# Sheet1.net
KiCad netlist of a schematic drawn in Altium Designer
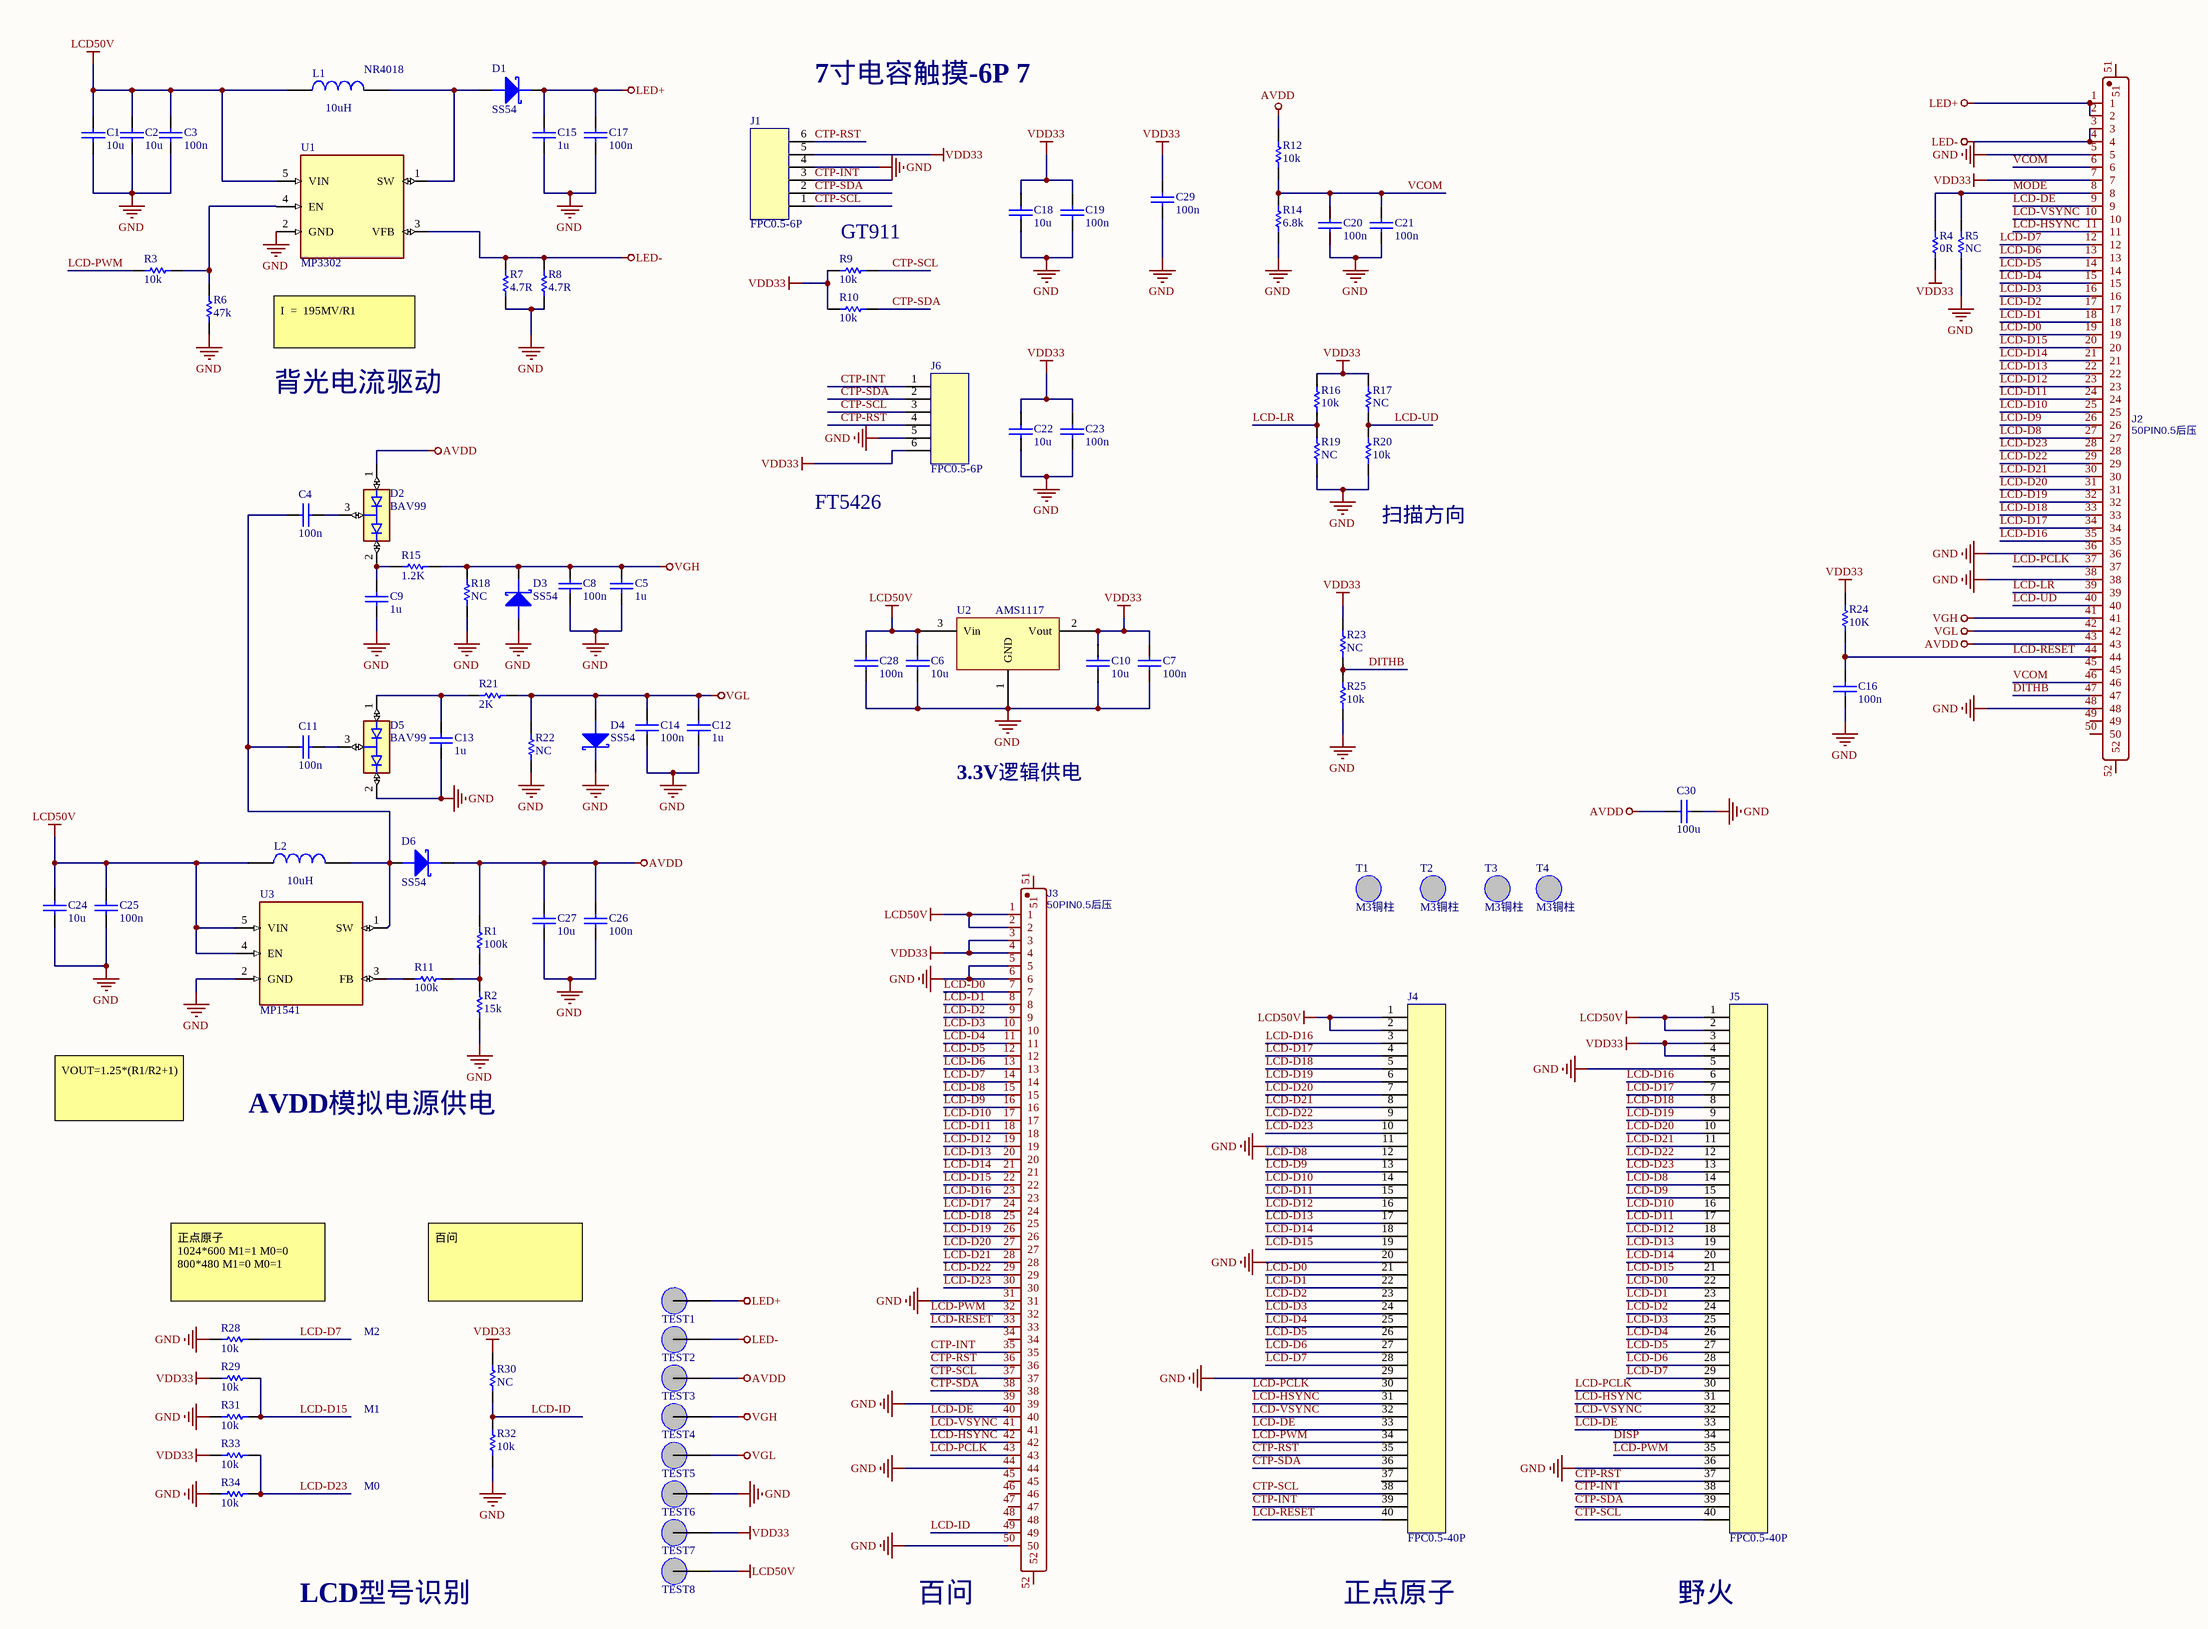
[diagram p0: Sheet1.SchDoc]

(export (version "E")
  (design (tool "Eeschema 10.0.6"))
  (components
    (comp (ref "C1")
      (value "10u")
      (footprint "0805C")
      (description "无极性电容")
      (libsource (lib "常用元件-电容") (part "CAP"))
    )
    (comp (ref "C2")
      (value "10u")
      (footprint "0805C")
      (description "无极性电容")
      (libsource (lib "常用元件-电容") (part "CAP"))
    )
    (comp (ref "C3")
      (value "100n")
      (footprint "0805C")
      (description "无极性电容")
      (libsource (lib "常用元件-电容") (part "CAP"))
    )
    (comp (ref "C4")
      (value "100n")
      (footprint "0805C")
      (description "无极性电容")
      (libsource (lib "常用元件-电容") (part "CAP"))
    )
    (comp (ref "C5")
      (value "1u")
      (footprint "0805C")
      (description "无极性电容")
      (libsource (lib "常用元件-电容") (part "CAP"))
    )
    (comp (ref "C6")
      (value "10u")
      (footprint "0805C")
      (description "无极性电容")
      (libsource (lib "常用元件-电容") (part "CAP"))
    )
    (comp (ref "C7")
      (value "100n")
      (footprint "0805C")
      (description "无极性电容")
      (libsource (lib "常用元件-电容") (part "CAP"))
    )
    (comp (ref "C8")
      (value "100n")
      (footprint "0805C")
      (description "无极性电容")
      (libsource (lib "常用元件-电容") (part "CAP"))
    )
    (comp (ref "C9")
      (value "1u")
      (footprint "0805C")
      (description "无极性电容")
      (libsource (lib "常用元件-电容") (part "CAP"))
    )
    (comp (ref "C10")
      (value "10u")
      (footprint "0805C")
      (description "无极性电容")
      (libsource (lib "常用元件-电容") (part "CAP"))
    )
    (comp (ref "C11")
      (value "100n")
      (footprint "0805C")
      (description "无极性电容")
      (libsource (lib "常用元件-电容") (part "CAP"))
    )
    (comp (ref "C12")
      (value "1u")
      (footprint "0805C")
      (description "无极性电容")
      (libsource (lib "常用元件-电容") (part "CAP"))
    )
    (comp (ref "C13")
      (value "1u")
      (footprint "0805C")
      (description "无极性电容")
      (libsource (lib "常用元件-电容") (part "CAP"))
    )
    (comp (ref "C14")
      (value "100n")
      (footprint "0805C")
      (description "无极性电容")
      (libsource (lib "常用元件-电容") (part "CAP"))
    )
    (comp (ref "C15")
      (value "1u")
      (footprint "0805C")
      (description "无极性电容")
      (libsource (lib "常用元件-电容") (part "CAP"))
    )
    (comp (ref "C16")
      (value "100n")
      (footprint "0805C")
      (description "无极性电容")
      (libsource (lib "常用元件-电容") (part "CAP"))
    )
    (comp (ref "C17")
      (value "100n")
      (footprint "0805C")
      (description "无极性电容")
      (libsource (lib "常用元件-电容") (part "CAP"))
    )
    (comp (ref "C18")
      (value "10u")
      (footprint "0805C")
      (description "无极性电容")
      (libsource (lib "常用元件-电容") (part "CAP"))
    )
    (comp (ref "C19")
      (value "100n")
      (footprint "0805C")
      (description "无极性电容")
      (libsource (lib "常用元件-电容") (part "CAP"))
    )
    (comp (ref "C20")
      (value "100n")
      (footprint "0805C")
      (description "无极性电容")
      (libsource (lib "常用元件-电容") (part "CAP"))
    )
    (comp (ref "C21")
      (value "100n")
      (footprint "0805C")
      (description "无极性电容")
      (libsource (lib "常用元件-电容") (part "CAP"))
    )
    (comp (ref "C22")
      (value "10u")
      (footprint "0805C")
      (description "无极性电容")
      (libsource (lib "常用元件-电容") (part "CAP"))
    )
    (comp (ref "C23")
      (value "100n")
      (footprint "0805C")
      (description "无极性电容")
      (libsource (lib "常用元件-电容") (part "CAP"))
    )
    (comp (ref "C24")
      (value "10u")
      (footprint "0805C")
      (description "无极性电容")
      (libsource (lib "常用元件-电容") (part "CAP"))
    )
    (comp (ref "C25")
      (value "100n")
      (footprint "0805C")
      (description "无极性电容")
      (libsource (lib "常用元件-电容") (part "CAP"))
    )
    (comp (ref "C26")
      (value "100n")
      (footprint "0805C")
      (description "无极性电容")
      (libsource (lib "常用元件-电容") (part "CAP"))
    )
    (comp (ref "C27")
      (value "10u")
      (footprint "0805C")
      (description "无极性电容")
      (libsource (lib "常用元件-电容") (part "CAP"))
    )
    (comp (ref "C28")
      (value "100n")
      (footprint "0805C")
      (description "无极性电容")
      (libsource (lib "常用元件-电容") (part "CAP"))
    )
    (comp (ref "C29")
      (value "100n")
      (footprint "0805C")
      (description "无极性电容")
      (libsource (lib "常用元件-电容") (part "CAP"))
    )
    (comp (ref "C30")
      (value "100u")
      (footprint "1206C")
      (description "无极性电容")
      (libsource (lib "常用元件-电容") (part "CAP"))
    )
    (comp (ref "D1")
      (value "SS54")
      (footprint "SOD-123")
      (description "肖特基二极管")
      (libsource (lib "常用元件-二极管") (part "DIODE SCHOTTKY"))
    )
    (comp (ref "D2")
      (value "BAV99")
      (footprint "BAV99:SOT23-3")
      (fields (field (name "MF") "{'manufacturer': u'ON Semiconductor'}"))
      (libsource (lib "*") (part "BAV99"))
    )
    (comp (ref "D3")
      (value "SS54")
      (footprint "SOD-123")
      (description "肖特基二极管")
      (libsource (lib "常用元件-二极管") (part "DIODE SCHOTTKY"))
    )
    (comp (ref "D4")
      (value "SS54")
      (footprint "SOD-123")
      (description "肖特基二极管")
      (libsource (lib "常用元件-二极管") (part "DIODE SCHOTTKY"))
    )
    (comp (ref "D5")
      (value "BAV99")
      (footprint "BAV99:SOT23-3")
      (fields (field (name "MF") "{'manufacturer': u'ON Semiconductor'}"))
      (libsource (lib "*") (part "BAV99"))
    )
    (comp (ref "D6")
      (value "SS54")
      (footprint "SOD-123")
      (description "肖特基二极管")
      (libsource (lib "常用元件-二极管") (part "DIODE SCHOTTKY"))
    )
    (comp (ref "J1")
      (value "FPC0.5-6P")
      (footprint "FPC0.5-6P")
      (description "贴片")
      (libsource (lib "") (part "FPC0.5-6P_1"))
    )
    (comp (ref "J2")
      (value "50PIN0.5后压")
      (footprint "FPC-SMD_KH-FG0.5-H2.0-50PIN")
      (fields (field (name "BOM_SUPPLIER PART") "C9900011403") (field (name "CONTRIBUTOR") "LCSC"))
      (libsource (lib "altium-import") (part "root_0_50PIN0.5后压_"))
    )
    (comp (ref "J3")
      (value "50PIN0.5后压")
      (footprint "FPC-SMD_KH-FG0.5-H2.0-50PIN")
      (fields (field (name "BOM_SUPPLIER PART") "C9900011403") (field (name "CONTRIBUTOR") "LCSC"))
      (libsource (lib "altium-import") (part "root_0_50PIN0.5后压_"))
    )
    (comp (ref "J4")
      (value "FPC0.5-40P")
      (footprint "FPC0.5-40P")
      (description "贴片")
      (libsource (lib "插接类-FPC") (part "FPC0.5-40P"))
    )
    (comp (ref "J5")
      (value "FPC0.5-40P")
      (footprint "FPC0.5-40P")
      (description "贴片")
      (libsource (lib "插接类-FPC") (part "FPC0.5-40P"))
    )
    (comp (ref "J6")
      (value "FPC0.5-6P")
      (footprint "FPC0.5-6P")
      (description "贴片")
      (libsource (lib "插接类-FPC") (part "FPC0.5-6P"))
    )
    (comp (ref "L1")
      (value "10uH")
      (footprint "CD42")
      (description "INDUCTOR")
      (libsource (lib "常用元件-电感") (part "INDUCTOR"))
    )
    (comp (ref "L2")
      (value "10uH")
      (footprint "CD42")
      (description "INDUCTOR")
      (libsource (lib "常用元件-电感") (part "INDUCTOR"))
    )
    (comp (ref "R1") (value "100k") (footprint "0805R") (libsource (lib "常用元件-电阻") (part "RES")))
    (comp (ref "R2") (value "15k") (footprint "0805R") (libsource (lib "常用元件-电阻") (part "RES")))
    (comp (ref "R3") (value "10k") (footprint "0805R") (libsource (lib "常用元件-电阻") (part "RES")))
    (comp (ref "R4") (value "0R") (footprint "0805R") (libsource (lib "常用元件-电阻") (part "RES")))
    (comp (ref "R5") (value "NC") (footprint "0805R") (libsource (lib "常用元件-电阻") (part "RES")))
    (comp (ref "R6") (value "47k") (footprint "0805R") (libsource (lib "常用元件-电阻") (part "RES")))
    (comp (ref "R7") (value "4.7R") (footprint "0805R") (libsource (lib "常用元件-电阻") (part "RES")))
    (comp (ref "R8") (value "4.7R") (footprint "0805R") (libsource (lib "常用元件-电阻") (part "RES")))
    (comp (ref "R9") (value "10k") (footprint "0805R") (libsource (lib "常用元件-电阻") (part "RES")))
    (comp (ref "R10") (value "10k") (footprint "0805R") (libsource (lib "常用元件-电阻") (part "RES")))
    (comp (ref "R11") (value "100k") (footprint "0805R") (libsource (lib "常用元件-电阻") (part "RES")))
    (comp (ref "R12") (value "10k") (footprint "0805R") (libsource (lib "常用元件-电阻") (part "RES")))
    (comp (ref "R14") (value "6.8k") (footprint "0805R") (libsource (lib "常用元件-电阻") (part "RES")))
    (comp (ref "R15") (value "1.2K") (footprint "0805R") (libsource (lib "常用元件-电阻") (part "RES")))
    (comp (ref "R16") (value "10k") (footprint "0805R") (libsource (lib "常用元件-电阻") (part "RES")))
    (comp (ref "R17") (value "NC") (footprint "0805R") (libsource (lib "常用元件-电阻") (part "RES")))
    (comp (ref "R18") (value "NC") (footprint "0805R") (libsource (lib "常用元件-电阻") (part "RES")))
    (comp (ref "R19") (value "NC") (footprint "0805R") (libsource (lib "常用元件-电阻") (part "RES")))
    (comp (ref "R20") (value "10k") (footprint "0805R") (libsource (lib "常用元件-电阻") (part "RES")))
    (comp (ref "R21") (value "2K") (footprint "0805R") (libsource (lib "常用元件-电阻") (part "RES")))
    (comp (ref "R22") (value "NC") (footprint "0805R") (libsource (lib "常用元件-电阻") (part "RES")))
    (comp (ref "R23") (value "NC") (footprint "0805R") (libsource (lib "常用元件-电阻") (part "RES")))
    (comp (ref "R24") (value "10K") (footprint "0805R") (libsource (lib "常用元件-电阻") (part "RES")))
    (comp (ref "R25") (value "10k") (footprint "0805R") (libsource (lib "常用元件-电阻") (part "RES")))
    (comp (ref "R28") (value "10k") (footprint "0805R") (libsource (lib "常用元件-电阻") (part "RES")))
    (comp (ref "R29") (value "10k") (footprint "0805R") (libsource (lib "常用元件-电阻") (part "RES")))
    (comp (ref "R30") (value "NC") (footprint "0805R") (libsource (lib "常用元件-电阻") (part "RES")))
    (comp (ref "R31") (value "10k") (footprint "0805R") (libsource (lib "常用元件-电阻") (part "RES")))
    (comp (ref "R32") (value "10k") (footprint "0805R") (libsource (lib "常用元件-电阻") (part "RES")))
    (comp (ref "R33") (value "10k") (footprint "0805R") (libsource (lib "常用元件-电阻") (part "RES")))
    (comp (ref "R34") (value "10k") (footprint "0805R") (libsource (lib "常用元件-电阻") (part "RES")))
    (comp (ref "T1") (value "M3铜柱") (footprint "M3 单孔") (libsource (lib "M3铜柱") (part "M3铜柱")))
    (comp (ref "T2") (value "M3铜柱") (footprint "M3 单孔") (libsource (lib "M3铜柱") (part "M3铜柱")))
    (comp (ref "T3") (value "M3铜柱") (footprint "M3 单孔") (libsource (lib "M3铜柱") (part "M3铜柱")))
    (comp (ref "T4") (value "M3铜柱") (footprint "M3 单孔") (libsource (lib "M3铜柱") (part "M3铜柱")))
    (comp (ref "TEST1")
      (value "TEST")
      (footprint "TEST TP1.4_G")
      (description "测试针")
      (fields (field (name "版权归属") "源创客"))
      (libsource (lib "测试类-测试针") (part "TEST"))
    )
    (comp (ref "TEST2")
      (value "TEST")
      (footprint "TEST TP1.4_G")
      (description "测试针")
      (fields (field (name "版权归属") "源创客"))
      (libsource (lib "测试类-测试针") (part "TEST"))
    )
    (comp (ref "TEST3")
      (value "TEST")
      (footprint "TEST TP1.4_G")
      (description "测试针")
      (fields (field (name "版权归属") "源创客"))
      (libsource (lib "测试类-测试针") (part "TEST"))
    )
    (comp (ref "TEST4")
      (value "TEST")
      (footprint "TEST TP1.4_G")
      (description "测试针")
      (fields (field (name "版权归属") "源创客"))
      (libsource (lib "测试类-测试针") (part "TEST"))
    )
    (comp (ref "TEST5")
      (value "TEST")
      (footprint "TEST TP1.4_G")
      (description "测试针")
      (fields (field (name "版权归属") "源创客"))
      (libsource (lib "测试类-测试针") (part "TEST"))
    )
    (comp (ref "TEST6")
      (value "TEST")
      (footprint "TEST TP1.4_G")
      (description "测试针")
      (fields (field (name "版权归属") "源创客"))
      (libsource (lib "测试类-测试针") (part "TEST"))
    )
    (comp (ref "TEST7")
      (value "TEST")
      (footprint "TEST TP1.4_G")
      (description "测试针")
      (fields (field (name "版权归属") "源创客"))
      (libsource (lib "测试类-测试针") (part "TEST"))
    )
    (comp (ref "TEST8")
      (value "TEST")
      (footprint "TEST TP1.4_G")
      (description "测试针")
      (fields (field (name "版权归属") "源创客"))
      (libsource (lib "测试类-测试针") (part "TEST"))
    )
    (comp (ref "U1")
      (value "MP3302")
      (footprint "SOT95P280X100-5N")
      (fields
        (field (name "MP") "TPS563201DDCR")
        (field (name "MF") "{'manufacturer': u'Texas Instruments'}")
      )
      (libsource (lib "MP3302") (part "MP3302"))
    )
    (comp (ref "U2")
      (value "AMS1117")
      (footprint "SOT223")
      (description "三端稳压芯片")
      (libsource (lib "芯片-电源芯片") (part "AMS1117"))
    )
    (comp (ref "U3")
      (value "MP1541")
      (footprint "SOT95P280X100-5N")
      (fields
        (field (name "MP") "TPS563201DDCR")
        (field (name "MF") "{'manufacturer': u'Texas Instruments'}")
      )
      (libsource (lib "MP1541") (part "MP1541"))
    )
  )
  (nets
    (net (code "1") (name "/CTP-INT") (class "Default")
      (node (ref "J1") (pin "3") (pinfunction "3_3") (pintype "passive"))
      (node (ref "J3") (pin "35") (pinfunction "35_35") (pintype "passive"))
      (node (ref "J4") (pin "39") (pinfunction "39_39") (pintype "passive"))
      (node (ref "J5") (pin "38") (pinfunction "38_38") (pintype "passive"))
      (node (ref "J6") (pin "1") (pinfunction "1_1") (pintype "passive"))
    )
    (net (code "2") (name "/CTP-RST") (class "Default")
      (node (ref "J1") (pin "6") (pinfunction "6_6") (pintype "passive"))
      (node (ref "J3") (pin "36") (pinfunction "36_36") (pintype "passive"))
      (node (ref "J4") (pin "35") (pinfunction "35_35") (pintype "passive"))
      (node (ref "J5") (pin "37") (pinfunction "37_37") (pintype "passive"))
      (node (ref "J6") (pin "4") (pinfunction "4_4") (pintype "passive"))
    )
    (net (code "3") (name "/CTP-SCL") (class "Default")
      (node (ref "J1") (pin "1") (pinfunction "1_1") (pintype "passive"))
      (node (ref "J3") (pin "37") (pinfunction "37_37") (pintype "passive"))
      (node (ref "J4") (pin "38") (pinfunction "38_38") (pintype "passive"))
      (node (ref "J5") (pin "40") (pinfunction "40_40") (pintype "passive"))
      (node (ref "J6") (pin "3") (pinfunction "3_3") (pintype "passive"))
      (node (ref "R9") (pin "1") (pinfunction "1_1") (pintype "passive"))
    )
    (net (code "4") (name "/CTP-SDA") (class "Default")
      (node (ref "J1") (pin "2") (pinfunction "2_2") (pintype "passive"))
      (node (ref "J3") (pin "38") (pinfunction "38_38") (pintype "passive"))
      (node (ref "J4") (pin "36") (pinfunction "36_36") (pintype "passive"))
      (node (ref "J5") (pin "39") (pinfunction "39_39") (pintype "passive"))
      (node (ref "J6") (pin "2") (pinfunction "2_2") (pintype "passive"))
      (node (ref "R10") (pin "1") (pinfunction "1_1") (pintype "passive"))
    )
    (net (code "5") (name "/DISP") (class "Default")
      (node (ref "J5") (pin "34") (pinfunction "34_34") (pintype "passive"))
    )
    (net (code "6") (name "/DITHB") (class "Default")
      (node (ref "J2") (pin "47") (pinfunction "47_47") (pintype "passive"))
      (node (ref "R23") (pin "2") (pinfunction "2_2") (pintype "passive"))
      (node (ref "R25") (pin "1") (pinfunction "1_1") (pintype "passive"))
    )
    (net (code "7") (name "/LCD-D0") (class "Default")
      (node (ref "J2") (pin "19") (pinfunction "19_19") (pintype "passive"))
      (node (ref "J3") (pin "7") (pinfunction "7_7") (pintype "passive"))
      (node (ref "J4") (pin "21") (pinfunction "21_21") (pintype "passive"))
      (node (ref "J5") (pin "22") (pinfunction "22_22") (pintype "passive"))
    )
    (net (code "8") (name "/LCD-D1") (class "Default")
      (node (ref "J2") (pin "18") (pinfunction "18_18") (pintype "passive"))
      (node (ref "J3") (pin "8") (pinfunction "8_8") (pintype "passive"))
      (node (ref "J4") (pin "22") (pinfunction "22_22") (pintype "passive"))
      (node (ref "J5") (pin "23") (pinfunction "23_23") (pintype "passive"))
    )
    (net (code "9") (name "/LCD-D2") (class "Default")
      (node (ref "J2") (pin "17") (pinfunction "17_17") (pintype "passive"))
      (node (ref "J3") (pin "9") (pinfunction "9_9") (pintype "passive"))
      (node (ref "J4") (pin "23") (pinfunction "23_23") (pintype "passive"))
      (node (ref "J5") (pin "24") (pinfunction "24_24") (pintype "passive"))
    )
    (net (code "10") (name "/LCD-D3") (class "Default")
      (node (ref "J2") (pin "16") (pinfunction "16_16") (pintype "passive"))
      (node (ref "J3") (pin "10") (pinfunction "10_10") (pintype "passive"))
      (node (ref "J4") (pin "24") (pinfunction "24_24") (pintype "passive"))
      (node (ref "J5") (pin "25") (pinfunction "25_25") (pintype "passive"))
    )
    (net (code "11") (name "/LCD-D4") (class "Default")
      (node (ref "J2") (pin "15") (pinfunction "15_15") (pintype "passive"))
      (node (ref "J3") (pin "11") (pinfunction "11_11") (pintype "passive"))
      (node (ref "J4") (pin "25") (pinfunction "25_25") (pintype "passive"))
      (node (ref "J5") (pin "26") (pinfunction "26_26") (pintype "passive"))
    )
    (net (code "12") (name "/LCD-D5") (class "Default")
      (node (ref "J2") (pin "14") (pinfunction "14_14") (pintype "passive"))
      (node (ref "J3") (pin "12") (pinfunction "12_12") (pintype "passive"))
      (node (ref "J4") (pin "26") (pinfunction "26_26") (pintype "passive"))
      (node (ref "J5") (pin "27") (pinfunction "27_27") (pintype "passive"))
    )
    (net (code "13") (name "/LCD-D6") (class "Default")
      (node (ref "J2") (pin "13") (pinfunction "13_13") (pintype "passive"))
      (node (ref "J3") (pin "13") (pinfunction "13_13") (pintype "passive"))
      (node (ref "J4") (pin "27") (pinfunction "27_27") (pintype "passive"))
      (node (ref "J5") (pin "28") (pinfunction "28_28") (pintype "passive"))
    )
    (net (code "14") (name "/LCD-D7") (class "Default")
      (node (ref "J2") (pin "12") (pinfunction "12_12") (pintype "passive"))
      (node (ref "J3") (pin "14") (pinfunction "14_14") (pintype "passive"))
      (node (ref "J4") (pin "28") (pinfunction "28_28") (pintype "passive"))
      (node (ref "J5") (pin "29") (pinfunction "29_29") (pintype "passive"))
      (node (ref "R28") (pin "2") (pinfunction "2_2") (pintype "passive"))
    )
    (net (code "15") (name "/LCD-D8") (class "Default")
      (node (ref "J2") (pin "27") (pinfunction "27_27") (pintype "passive"))
      (node (ref "J3") (pin "15") (pinfunction "15_15") (pintype "passive"))
      (node (ref "J4") (pin "12") (pinfunction "12_12") (pintype "passive"))
      (node (ref "J5") (pin "14") (pinfunction "14_14") (pintype "passive"))
    )
    (net (code "16") (name "/LCD-D9") (class "Default")
      (node (ref "J2") (pin "26") (pinfunction "26_26") (pintype "passive"))
      (node (ref "J3") (pin "16") (pinfunction "16_16") (pintype "passive"))
      (node (ref "J4") (pin "13") (pinfunction "13_13") (pintype "passive"))
      (node (ref "J5") (pin "15") (pinfunction "15_15") (pintype "passive"))
    )
    (net (code "17") (name "/LCD-D10") (class "Default")
      (node (ref "J2") (pin "25") (pinfunction "25_25") (pintype "passive"))
      (node (ref "J3") (pin "17") (pinfunction "17_17") (pintype "passive"))
      (node (ref "J4") (pin "14") (pinfunction "14_14") (pintype "passive"))
      (node (ref "J5") (pin "16") (pinfunction "16_16") (pintype "passive"))
    )
    (net (code "18") (name "/LCD-D11") (class "Default")
      (node (ref "J2") (pin "24") (pinfunction "24_24") (pintype "passive"))
      (node (ref "J3") (pin "18") (pinfunction "18_18") (pintype "passive"))
      (node (ref "J4") (pin "15") (pinfunction "15_15") (pintype "passive"))
      (node (ref "J5") (pin "17") (pinfunction "17_17") (pintype "passive"))
    )
    (net (code "19") (name "/LCD-D12") (class "Default")
      (node (ref "J2") (pin "23") (pinfunction "23_23") (pintype "passive"))
      (node (ref "J3") (pin "19") (pinfunction "19_19") (pintype "passive"))
      (node (ref "J4") (pin "16") (pinfunction "16_16") (pintype "passive"))
      (node (ref "J5") (pin "18") (pinfunction "18_18") (pintype "passive"))
    )
    (net (code "20") (name "/LCD-D13") (class "Default")
      (node (ref "J2") (pin "22") (pinfunction "22_22") (pintype "passive"))
      (node (ref "J3") (pin "20") (pinfunction "20_20") (pintype "passive"))
      (node (ref "J4") (pin "17") (pinfunction "17_17") (pintype "passive"))
      (node (ref "J5") (pin "19") (pinfunction "19_19") (pintype "passive"))
    )
    (net (code "21") (name "/LCD-D14") (class "Default")
      (node (ref "J2") (pin "21") (pinfunction "21_21") (pintype "passive"))
      (node (ref "J3") (pin "21") (pinfunction "21_21") (pintype "passive"))
      (node (ref "J4") (pin "18") (pinfunction "18_18") (pintype "passive"))
      (node (ref "J5") (pin "20") (pinfunction "20_20") (pintype "passive"))
    )
    (net (code "22") (name "/LCD-D15") (class "Default")
      (node (ref "J2") (pin "20") (pinfunction "20_20") (pintype "passive"))
      (node (ref "J3") (pin "22") (pinfunction "22_22") (pintype "passive"))
      (node (ref "J4") (pin "19") (pinfunction "19_19") (pintype "passive"))
      (node (ref "J5") (pin "21") (pinfunction "21_21") (pintype "passive"))
      (node (ref "R29") (pin "2") (pinfunction "2_2") (pintype "passive"))
      (node (ref "R31") (pin "1") (pinfunction "1_1") (pintype "passive"))
    )
    (net (code "23") (name "/LCD-D16") (class "Default")
      (node (ref "J2") (pin "35") (pinfunction "35_35") (pintype "passive"))
      (node (ref "J3") (pin "23") (pinfunction "23_23") (pintype "passive"))
      (node (ref "J4") (pin "3") (pinfunction "3_3") (pintype "passive"))
      (node (ref "J5") (pin "6") (pinfunction "6_6") (pintype "passive"))
    )
    (net (code "24") (name "/LCD-D17") (class "Default")
      (node (ref "J2") (pin "34") (pinfunction "34_34") (pintype "passive"))
      (node (ref "J3") (pin "24") (pinfunction "24_24") (pintype "passive"))
      (node (ref "J4") (pin "4") (pinfunction "4_4") (pintype "passive"))
      (node (ref "J5") (pin "7") (pinfunction "7_7") (pintype "passive"))
    )
    (net (code "25") (name "/LCD-D18") (class "Default")
      (node (ref "J2") (pin "33") (pinfunction "33_33") (pintype "passive"))
      (node (ref "J3") (pin "25") (pinfunction "25_25") (pintype "passive"))
      (node (ref "J4") (pin "5") (pinfunction "5_5") (pintype "passive"))
      (node (ref "J5") (pin "8") (pinfunction "8_8") (pintype "passive"))
    )
    (net (code "26") (name "/LCD-D19") (class "Default")
      (node (ref "J2") (pin "32") (pinfunction "32_32") (pintype "passive"))
      (node (ref "J3") (pin "26") (pinfunction "26_26") (pintype "passive"))
      (node (ref "J4") (pin "6") (pinfunction "6_6") (pintype "passive"))
      (node (ref "J5") (pin "9") (pinfunction "9_9") (pintype "passive"))
    )
    (net (code "27") (name "/LCD-D20") (class "Default")
      (node (ref "J2") (pin "31") (pinfunction "31_31") (pintype "passive"))
      (node (ref "J3") (pin "27") (pinfunction "27_27") (pintype "passive"))
      (node (ref "J4") (pin "7") (pinfunction "7_7") (pintype "passive"))
      (node (ref "J5") (pin "10") (pinfunction "10_10") (pintype "passive"))
    )
    (net (code "28") (name "/LCD-D21") (class "Default")
      (node (ref "J2") (pin "30") (pinfunction "30_30") (pintype "passive"))
      (node (ref "J3") (pin "28") (pinfunction "28_28") (pintype "passive"))
      (node (ref "J4") (pin "8") (pinfunction "8_8") (pintype "passive"))
      (node (ref "J5") (pin "11") (pinfunction "11_11") (pintype "passive"))
    )
    (net (code "29") (name "/LCD-D22") (class "Default")
      (node (ref "J2") (pin "29") (pinfunction "29_29") (pintype "passive"))
      (node (ref "J3") (pin "29") (pinfunction "29_29") (pintype "passive"))
      (node (ref "J4") (pin "9") (pinfunction "9_9") (pintype "passive"))
      (node (ref "J5") (pin "12") (pinfunction "12_12") (pintype "passive"))
    )
    (net (code "30") (name "/LCD-D23") (class "Default")
      (node (ref "J2") (pin "28") (pinfunction "28_28") (pintype "passive"))
      (node (ref "J3") (pin "30") (pinfunction "30_30") (pintype "passive"))
      (node (ref "J4") (pin "10") (pinfunction "10_10") (pintype "passive"))
      (node (ref "J5") (pin "13") (pinfunction "13_13") (pintype "passive"))
      (node (ref "R33") (pin "2") (pinfunction "2_2") (pintype "passive"))
      (node (ref "R34") (pin "1") (pinfunction "1_1") (pintype "passive"))
    )
    (net (code "31") (name "/LCD-DE") (class "Default")
      (node (ref "J2") (pin "9") (pinfunction "9_9") (pintype "passive"))
      (node (ref "J3") (pin "40") (pinfunction "40_40") (pintype "passive"))
      (node (ref "J4") (pin "33") (pinfunction "33_33") (pintype "passive"))
      (node (ref "J5") (pin "33") (pinfunction "33_33") (pintype "passive"))
    )
    (net (code "32") (name "/LCD-HSYNC") (class "Default")
      (node (ref "J2") (pin "11") (pinfunction "11_11") (pintype "passive"))
      (node (ref "J3") (pin "42") (pinfunction "42_42") (pintype "passive"))
      (node (ref "J4") (pin "31") (pinfunction "31_31") (pintype "passive"))
      (node (ref "J5") (pin "31") (pinfunction "31_31") (pintype "passive"))
    )
    (net (code "33") (name "/LCD-ID") (class "Default")
      (node (ref "J3") (pin "49") (pinfunction "49_49") (pintype "passive"))
      (node (ref "R30") (pin "2") (pinfunction "2_2") (pintype "passive"))
      (node (ref "R32") (pin "2") (pinfunction "2_2") (pintype "passive"))
    )
    (net (code "34") (name "/LCD-LR") (class "Default")
      (node (ref "J2") (pin "39") (pinfunction "39_39") (pintype "passive"))
      (node (ref "R16") (pin "2") (pinfunction "2_2") (pintype "passive"))
      (node (ref "R19") (pin "1") (pinfunction "1_1") (pintype "passive"))
    )
    (net (code "35") (name "/LCD-PCLK") (class "Default")
      (node (ref "J2") (pin "37") (pinfunction "37_37") (pintype "passive"))
      (node (ref "J3") (pin "43") (pinfunction "43_43") (pintype "passive"))
      (node (ref "J4") (pin "30") (pinfunction "30_30") (pintype "passive"))
      (node (ref "J5") (pin "30") (pinfunction "30_30") (pintype "passive"))
    )
    (net (code "36") (name "/LCD-PWM") (class "Default")
      (node (ref "J3") (pin "32") (pinfunction "32_32") (pintype "passive"))
      (node (ref "J4") (pin "34") (pinfunction "34_34") (pintype "passive"))
      (node (ref "J5") (pin "35") (pinfunction "35_35") (pintype "passive"))
      (node (ref "R3") (pin "1") (pinfunction "1_1") (pintype "passive"))
    )
    (net (code "37") (name "/LCD-RESET") (class "Default")
      (node (ref "C16") (pin "2") (pinfunction "2_2") (pintype "passive"))
      (node (ref "J2") (pin "44") (pinfunction "44_44") (pintype "passive"))
      (node (ref "J3") (pin "33") (pinfunction "33_33") (pintype "passive"))
      (node (ref "J4") (pin "40") (pinfunction "40_40") (pintype "passive"))
      (node (ref "R24") (pin "2") (pinfunction "2_2") (pintype "passive"))
    )
    (net (code "38") (name "/LCD-UD") (class "Default")
      (node (ref "J2") (pin "40") (pinfunction "40_40") (pintype "passive"))
      (node (ref "R17") (pin "2") (pinfunction "2_2") (pintype "passive"))
      (node (ref "R20") (pin "1") (pinfunction "1_1") (pintype "passive"))
    )
    (net (code "39") (name "/LCD-VSYNC") (class "Default")
      (node (ref "J2") (pin "10") (pinfunction "10_10") (pintype "passive"))
      (node (ref "J3") (pin "41") (pinfunction "41_41") (pintype "passive"))
      (node (ref "J4") (pin "32") (pinfunction "32_32") (pintype "passive"))
      (node (ref "J5") (pin "32") (pinfunction "32_32") (pintype "passive"))
    )
    (net (code "40") (name "/MODE") (class "Default")
      (node (ref "J2") (pin "8") (pinfunction "8_8") (pintype "passive"))
      (node (ref "R4") (pin "1") (pinfunction "1_1") (pintype "passive"))
      (node (ref "R5") (pin "1") (pinfunction "1_1") (pintype "passive"))
    )
    (net (code "41") (name "/VCOM") (class "Default")
      (node (ref "C20") (pin "2") (pinfunction "2_2") (pintype "passive"))
      (node (ref "C21") (pin "2") (pinfunction "2_2") (pintype "passive"))
      (node (ref "J2") (pin "46") (pinfunction "46_46") (pintype "passive"))
      (node (ref "J2") (pin "6") (pinfunction "6_6") (pintype "passive"))
      (node (ref "R12") (pin "2") (pinfunction "2_2") (pintype "passive"))
      (node (ref "R14") (pin "1") (pinfunction "1_1") (pintype "passive"))
    )
    (net (code "42") (name "AVDD") (class "Default")
      (node (ref "C26") (pin "2") (pinfunction "2_2") (pintype "passive"))
      (node (ref "C27") (pin "2") (pinfunction "2_2") (pintype "passive"))
      (node (ref "C30") (pin "1") (pinfunction "1_1") (pintype "passive"))
      (node (ref "D2") (pin "1") (pinfunction "A1_1") (pintype "bidirectional"))
      (node (ref "D6") (pin "K") (pinfunction "K_K") (pintype "passive"))
      (node (ref "J2") (pin "43") (pinfunction "43_43") (pintype "passive"))
      (node (ref "R1") (pin "1") (pinfunction "1_1") (pintype "passive"))
      (node (ref "R12") (pin "1") (pinfunction "1_1") (pintype "passive"))
      (node (ref "TEST3") (pin "1") (pinfunction "1_1") (pintype "passive"))
    )
    (net (code "43") (name "GND") (class "Default")
      (node (ref "C1") (pin "1") (pinfunction "1_1") (pintype "passive"))
      (node (ref "C10") (pin "1") (pinfunction "1_1") (pintype "passive"))
      (node (ref "C12") (pin "1") (pinfunction "1_1") (pintype "passive"))
      (node (ref "C13") (pin "2") (pinfunction "2_2") (pintype "passive"))
      (node (ref "C14") (pin "1") (pinfunction "1_1") (pintype "passive"))
      (node (ref "C15") (pin "1") (pinfunction "1_1") (pintype "passive"))
      (node (ref "C16") (pin "1") (pinfunction "1_1") (pintype "passive"))
      (node (ref "C17") (pin "1") (pinfunction "1_1") (pintype "passive"))
      (node (ref "C18") (pin "1") (pinfunction "1_1") (pintype "passive"))
      (node (ref "C19") (pin "1") (pinfunction "1_1") (pintype "passive"))
      (node (ref "C2") (pin "1") (pinfunction "1_1") (pintype "passive"))
      (node (ref "C20") (pin "1") (pinfunction "1_1") (pintype "passive"))
      (node (ref "C21") (pin "1") (pinfunction "1_1") (pintype "passive"))
      (node (ref "C22") (pin "1") (pinfunction "1_1") (pintype "passive"))
      (node (ref "C23") (pin "1") (pinfunction "1_1") (pintype "passive"))
      (node (ref "C24") (pin "1") (pinfunction "1_1") (pintype "passive"))
      (node (ref "C25") (pin "1") (pinfunction "1_1") (pintype "passive"))
      (node (ref "C26") (pin "1") (pinfunction "1_1") (pintype "passive"))
      (node (ref "C27") (pin "1") (pinfunction "1_1") (pintype "passive"))
      (node (ref "C28") (pin "1") (pinfunction "1_1") (pintype "passive"))
      (node (ref "C29") (pin "1") (pinfunction "1_1") (pintype "passive"))
      (node (ref "C3") (pin "1") (pinfunction "1_1") (pintype "passive"))
      (node (ref "C30") (pin "2") (pinfunction "2_2") (pintype "passive"))
      (node (ref "C5") (pin "1") (pinfunction "1_1") (pintype "passive"))
      (node (ref "C6") (pin "1") (pinfunction "1_1") (pintype "passive"))
      (node (ref "C7") (pin "1") (pinfunction "1_1") (pintype "passive"))
      (node (ref "C8") (pin "1") (pinfunction "1_1") (pintype "passive"))
      (node (ref "C9") (pin "1") (pinfunction "1_1") (pintype "passive"))
      (node (ref "D3") (pin "A") (pinfunction "A_A") (pintype "passive"))
      (node (ref "D4") (pin "K") (pinfunction "K_K") (pintype "passive"))
      (node (ref "D5") (pin "2") (pinfunction "C2_2") (pintype "bidirectional"))
      (node (ref "J1") (pin "4") (pinfunction "4_4") (pintype "passive"))
      (node (ref "J2") (pin "36") (pinfunction "36_36") (pintype "passive"))
      (node (ref "J2") (pin "38") (pinfunction "38_38") (pintype "passive"))
      (node (ref "J2") (pin "48") (pinfunction "48_48") (pintype "passive"))
      (node (ref "J2") (pin "5") (pinfunction "5_5") (pintype "passive"))
      (node (ref "J3") (pin "31") (pinfunction "31_31") (pintype "passive"))
      (node (ref "J3") (pin "39") (pinfunction "39_39") (pintype "passive"))
      (node (ref "J3") (pin "44") (pinfunction "44_44") (pintype "passive"))
      (node (ref "J3") (pin "5") (pinfunction "5_5") (pintype "passive"))
      (node (ref "J3") (pin "50") (pinfunction "50_50") (pintype "passive"))
      (node (ref "J3") (pin "6") (pinfunction "6_6") (pintype "passive"))
      (node (ref "J4") (pin "11") (pinfunction "11_11") (pintype "passive"))
      (node (ref "J4") (pin "20") (pinfunction "20_20") (pintype "passive"))
      (node (ref "J4") (pin "29") (pinfunction "29_29") (pintype "passive"))
      (node (ref "J5") (pin "36") (pinfunction "36_36") (pintype "passive"))
      (node (ref "J5") (pin "5") (pinfunction "5_5") (pintype "passive"))
      (node (ref "J6") (pin "5") (pinfunction "5_5") (pintype "passive"))
      (node (ref "R14") (pin "2") (pinfunction "2_2") (pintype "passive"))
      (node (ref "R18") (pin "1") (pinfunction "1_1") (pintype "passive"))
      (node (ref "R19") (pin "2") (pinfunction "2_2") (pintype "passive"))
      (node (ref "R2") (pin "1") (pinfunction "1_1") (pintype "passive"))
      (node (ref "R20") (pin "2") (pinfunction "2_2") (pintype "passive"))
      (node (ref "R22") (pin "1") (pinfunction "1_1") (pintype "passive"))
      (node (ref "R25") (pin "2") (pinfunction "2_2") (pintype "passive"))
      (node (ref "R28") (pin "1") (pinfunction "1_1") (pintype "passive"))
      (node (ref "R31") (pin "2") (pinfunction "2_2") (pintype "passive"))
      (node (ref "R32") (pin "1") (pinfunction "1_1") (pintype "passive"))
      (node (ref "R34") (pin "2") (pinfunction "2_2") (pintype "passive"))
      (node (ref "R5") (pin "2") (pinfunction "2_2") (pintype "passive"))
      (node (ref "R6") (pin "1") (pinfunction "1_1") (pintype "passive"))
      (node (ref "R7") (pin "1") (pinfunction "1_1") (pintype "passive"))
      (node (ref "R8") (pin "1") (pinfunction "1_1") (pintype "passive"))
      (node (ref "TEST6") (pin "1") (pinfunction "1_1") (pintype "passive"))
      (node (ref "U1") (pin "2") (pinfunction "GND_2") (pintype "input"))
      (node (ref "U2") (pin "1") (pinfunction "GND_1") (pintype "passive"))
      (node (ref "U3") (pin "2") (pinfunction "GND_2") (pintype "input"))
    )
    (net (code "44") (name "LCD50V") (class "Default")
      (node (ref "C1") (pin "2") (pinfunction "2_2") (pintype "passive"))
      (node (ref "C2") (pin "2") (pinfunction "2_2") (pintype "passive"))
      (node (ref "C24") (pin "2") (pinfunction "2_2") (pintype "passive"))
      (node (ref "C25") (pin "2") (pinfunction "2_2") (pintype "passive"))
      (node (ref "C28") (pin "2") (pinfunction "2_2") (pintype "passive"))
      (node (ref "C3") (pin "2") (pinfunction "2_2") (pintype "passive"))
      (node (ref "C6") (pin "2") (pinfunction "2_2") (pintype "passive"))
      (node (ref "J3") (pin "1") (pinfunction "1_1") (pintype "passive"))
      (node (ref "J3") (pin "2") (pinfunction "2_2") (pintype "passive"))
      (node (ref "J4") (pin "1") (pinfunction "1_1") (pintype "passive"))
      (node (ref "J4") (pin "2") (pinfunction "2_2") (pintype "passive"))
      (node (ref "J5") (pin "1") (pinfunction "1_1") (pintype "passive"))
      (node (ref "J5") (pin "2") (pinfunction "2_2") (pintype "passive"))
      (node (ref "L1") (pin "1") (pinfunction "1_1") (pintype "passive"))
      (node (ref "L2") (pin "1") (pinfunction "1_1") (pintype "passive"))
      (node (ref "TEST8") (pin "1") (pinfunction "1_1") (pintype "passive"))
      (node (ref "U1") (pin "5") (pinfunction "VIN_5") (pintype "input"))
      (node (ref "U2") (pin "3") (pinfunction "Vin_3") (pintype "passive"))
      (node (ref "U3") (pin "4") (pinfunction "EN_4") (pintype "input"))
      (node (ref "U3") (pin "5") (pinfunction "VIN_5") (pintype "input"))
    )
    (net (code "45") (name "LED+") (class "Default")
      (node (ref "C15") (pin "2") (pinfunction "2_2") (pintype "passive"))
      (node (ref "C17") (pin "2") (pinfunction "2_2") (pintype "passive"))
      (node (ref "D1") (pin "K") (pinfunction "K_K") (pintype "passive"))
      (node (ref "J2") (pin "1") (pinfunction "1_1") (pintype "passive"))
      (node (ref "J2") (pin "2") (pinfunction "2_2") (pintype "passive"))
      (node (ref "TEST1") (pin "1") (pinfunction "1_1") (pintype "passive"))
    )
    (net (code "46") (name "LED-") (class "Default")
      (node (ref "J2") (pin "3") (pinfunction "3_3") (pintype "passive"))
      (node (ref "J2") (pin "4") (pinfunction "4_4") (pintype "passive"))
      (node (ref "R7") (pin "2") (pinfunction "2_2") (pintype "passive"))
      (node (ref "R8") (pin "2") (pinfunction "2_2") (pintype "passive"))
      (node (ref "TEST2") (pin "1") (pinfunction "1_1") (pintype "passive"))
      (node (ref "U1") (pin "3") (pinfunction "VFB_3") (pintype "bidirectional"))
    )
    (net (code "47") (name "Net-(D2-C2)") (class "Default")
      (node (ref "C9") (pin "2") (pinfunction "2_2") (pintype "passive"))
      (node (ref "D2") (pin "2") (pinfunction "C2_2") (pintype "bidirectional"))
      (node (ref "R15") (pin "1") (pinfunction "1_1") (pintype "passive"))
    )
    (net (code "48") (name "Net-(D2-COM)") (class "Default")
      (node (ref "C4") (pin "1") (pinfunction "1_1") (pintype "passive"))
      (node (ref "D2") (pin "3") (pinfunction "COM_3") (pintype "bidirectional"))
    )
    (net (code "49") (name "Net-(D5-A1)") (class "Default")
      (node (ref "C13") (pin "1") (pinfunction "1_1") (pintype "passive"))
      (node (ref "D5") (pin "1") (pinfunction "A1_1") (pintype "bidirectional"))
      (node (ref "R21") (pin "1") (pinfunction "1_1") (pintype "passive"))
    )
    (net (code "50") (name "Net-(D5-COM)") (class "Default")
      (node (ref "C11") (pin "1") (pinfunction "1_1") (pintype "passive"))
      (node (ref "D5") (pin "3") (pinfunction "COM_3") (pintype "bidirectional"))
    )
    (net (code "51") (name "Net-(R1-Pad2)") (class "Default")
      (node (ref "R1") (pin "2") (pinfunction "2_2") (pintype "passive"))
      (node (ref "R11") (pin "2") (pinfunction "2_2") (pintype "passive"))
      (node (ref "R2") (pin "2") (pinfunction "2_2") (pintype "passive"))
    )
    (net (code "52") (name "Net-(U1-EN)") (class "Default")
      (node (ref "R3") (pin "2") (pinfunction "2_2") (pintype "passive"))
      (node (ref "R6") (pin "2") (pinfunction "2_2") (pintype "passive"))
      (node (ref "U1") (pin "4") (pinfunction "EN_4") (pintype "input"))
    )
    (net (code "53") (name "Net-(U1-SW)") (class "Default")
      (node (ref "D1") (pin "A") (pinfunction "A_A") (pintype "passive"))
      (node (ref "L1") (pin "2") (pinfunction "2_2") (pintype "passive"))
      (node (ref "U1") (pin "1") (pinfunction "SW_1") (pintype "bidirectional"))
    )
    (net (code "54") (name "Net-(U3-FB)") (class "Default")
      (node (ref "R11") (pin "1") (pinfunction "1_1") (pintype "passive"))
      (node (ref "U3") (pin "3") (pinfunction "FB_3") (pintype "bidirectional"))
    )
    (net (code "55") (name "Net-(U3-SW)") (class "Default")
      (node (ref "C11") (pin "2") (pinfunction "2_2") (pintype "passive"))
      (node (ref "C4") (pin "2") (pinfunction "2_2") (pintype "passive"))
      (node (ref "D6") (pin "A") (pinfunction "A_A") (pintype "passive"))
      (node (ref "L2") (pin "2") (pinfunction "2_2") (pintype "passive"))
      (node (ref "U3") (pin "1") (pinfunction "SW_1") (pintype "bidirectional"))
    )
    (net (code "56") (name "VDD33") (class "Default")
      (node (ref "C10") (pin "2") (pinfunction "2_2") (pintype "passive"))
      (node (ref "C18") (pin "2") (pinfunction "2_2") (pintype "passive"))
      (node (ref "C19") (pin "2") (pinfunction "2_2") (pintype "passive"))
      (node (ref "C22") (pin "2") (pinfunction "2_2") (pintype "passive"))
      (node (ref "C23") (pin "2") (pinfunction "2_2") (pintype "passive"))
      (node (ref "C29") (pin "2") (pinfunction "2_2") (pintype "passive"))
      (node (ref "C7") (pin "2") (pinfunction "2_2") (pintype "passive"))
      (node (ref "J1") (pin "5") (pinfunction "5_5") (pintype "passive"))
      (node (ref "J2") (pin "7") (pinfunction "7_7") (pintype "passive"))
      (node (ref "J3") (pin "3") (pinfunction "3_3") (pintype "passive"))
      (node (ref "J3") (pin "4") (pinfunction "4_4") (pintype "passive"))
      (node (ref "J5") (pin "3") (pinfunction "3_3") (pintype "passive"))
      (node (ref "J5") (pin "4") (pinfunction "4_4") (pintype "passive"))
      (node (ref "J6") (pin "6") (pinfunction "6_6") (pintype "passive"))
      (node (ref "R10") (pin "2") (pinfunction "2_2") (pintype "passive"))
      (node (ref "R16") (pin "1") (pinfunction "1_1") (pintype "passive"))
      (node (ref "R17") (pin "1") (pinfunction "1_1") (pintype "passive"))
      (node (ref "R23") (pin "1") (pinfunction "1_1") (pintype "passive"))
      (node (ref "R24") (pin "1") (pinfunction "1_1") (pintype "passive"))
      (node (ref "R29") (pin "1") (pinfunction "1_1") (pintype "passive"))
      (node (ref "R30") (pin "1") (pinfunction "1_1") (pintype "passive"))
      (node (ref "R33") (pin "1") (pinfunction "1_1") (pintype "passive"))
      (node (ref "R4") (pin "2") (pinfunction "2_2") (pintype "passive"))
      (node (ref "R9") (pin "2") (pinfunction "2_2") (pintype "passive"))
      (node (ref "TEST7") (pin "1") (pinfunction "1_1") (pintype "passive"))
      (node (ref "U2") (pin "2") (pinfunction "Vout_2") (pintype "passive"))
    )
    (net (code "57") (name "VGH") (class "Default")
      (node (ref "C5") (pin "2") (pinfunction "2_2") (pintype "passive"))
      (node (ref "C8") (pin "2") (pinfunction "2_2") (pintype "passive"))
      (node (ref "D3") (pin "K") (pinfunction "K_K") (pintype "passive"))
      (node (ref "J2") (pin "41") (pinfunction "41_41") (pintype "passive"))
      (node (ref "R15") (pin "2") (pinfunction "2_2") (pintype "passive"))
      (node (ref "R18") (pin "2") (pinfunction "2_2") (pintype "passive"))
      (node (ref "TEST4") (pin "1") (pinfunction "1_1") (pintype "passive"))
    )
    (net (code "58") (name "VGL") (class "Default")
      (node (ref "C12") (pin "2") (pinfunction "2_2") (pintype "passive"))
      (node (ref "C14") (pin "2") (pinfunction "2_2") (pintype "passive"))
      (node (ref "D4") (pin "A") (pinfunction "A_A") (pintype "passive"))
      (node (ref "J2") (pin "42") (pinfunction "42_42") (pintype "passive"))
      (node (ref "R21") (pin "2") (pinfunction "2_2") (pintype "passive"))
      (node (ref "R22") (pin "2") (pinfunction "2_2") (pintype "passive"))
      (node (ref "TEST5") (pin "1") (pinfunction "1_1") (pintype "passive"))
    )
    (net (code "59") (name "unconnected-(J2-Pad45)") (class "Default")
      (node (ref "J2") (pin "45") (pinfunction "45_45") (pintype "passive"))
    )
    (net (code "60") (name "unconnected-(J2-Pad49)") (class "Default")
      (node (ref "J2") (pin "49") (pinfunction "49_49") (pintype "passive"))
    )
    (net (code "61") (name "unconnected-(J2-Pad50)") (class "Default")
      (node (ref "J2") (pin "50") (pinfunction "50_50") (pintype "passive"))
    )
    (net (code "62") (name "unconnected-(J2-Pad51)") (class "Default")
      (node (ref "J2") (pin "51") (pinfunction "51_51") (pintype "passive"))
    )
    (net (code "63") (name "unconnected-(J2-Pad52)") (class "Default")
      (node (ref "J2") (pin "52") (pinfunction "52_52") (pintype "passive"))
    )
    (net (code "64") (name "unconnected-(J3-Pad34)") (class "Default")
      (node (ref "J3") (pin "34") (pinfunction "34_34") (pintype "passive"))
    )
    (net (code "65") (name "unconnected-(J3-Pad45)") (class "Default")
      (node (ref "J3") (pin "45") (pinfunction "45_45") (pintype "passive"))
    )
    (net (code "66") (name "unconnected-(J3-Pad46)") (class "Default")
      (node (ref "J3") (pin "46") (pinfunction "46_46") (pintype "passive"))
    )
    (net (code "67") (name "unconnected-(J3-Pad47)") (class "Default")
      (node (ref "J3") (pin "47") (pinfunction "47_47") (pintype "passive"))
    )
    (net (code "68") (name "unconnected-(J3-Pad48)") (class "Default")
      (node (ref "J3") (pin "48") (pinfunction "48_48") (pintype "passive"))
    )
    (net (code "69") (name "unconnected-(J3-Pad51)") (class "Default")
      (node (ref "J3") (pin "51") (pinfunction "51_51") (pintype "passive"))
    )
    (net (code "70") (name "unconnected-(J3-Pad52)") (class "Default")
      (node (ref "J3") (pin "52") (pinfunction "52_52") (pintype "passive"))
    )
    (net (code "71") (name "unconnected-(J4-Pad37)") (class "Default")
      (node (ref "J4") (pin "37") (pinfunction "37_37") (pintype "passive"))
    )
  )
)
